# Sheet1.net
KiCad netlist of a schematic drawn in Altium Designer
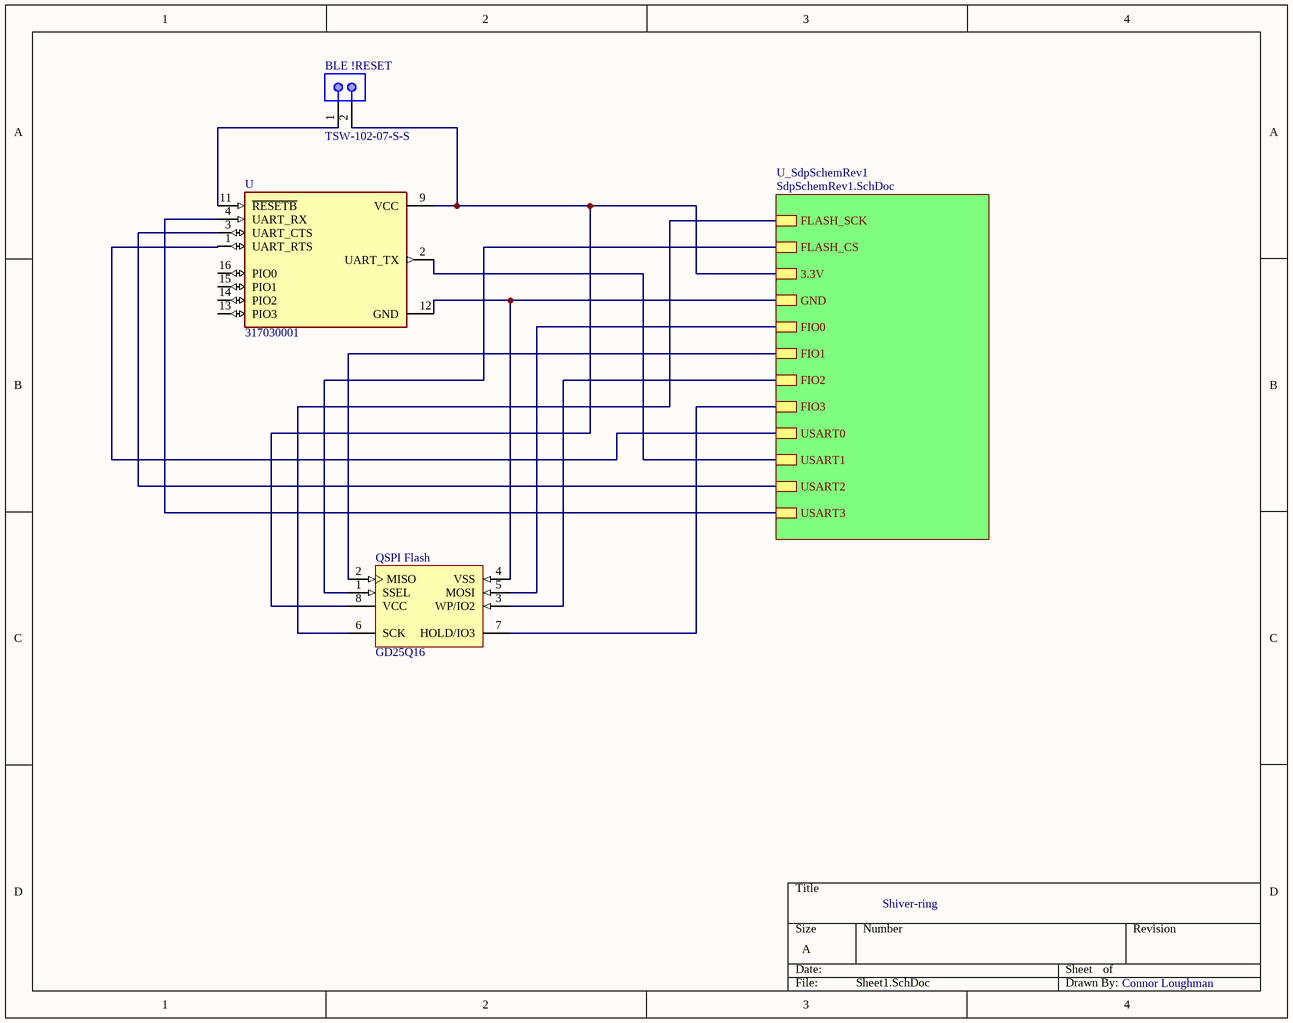
[diagram p0: Sheet1.SchDoc]

(export (version "E")
  (design (tool "Eeschema 10.0.6"))
  (components
    (comp (ref "BLE !RESET")
      (value "TSW-102-07-S-S")
      (footprint "SMTC-TSW-102-07-S-S")
      (fields (field (name "MANUFACTURER") "Samtec"))
      (libsource (lib "Altium Content Vault") (part "CN-1P-M-R2"))
    )
    (comp (ref "QSPI Flash")
      (value "GD25Q16")
      (footprint "MICT-MN-8_N")
      (fields
        (field (name "VOLTAGE") "2.7V-3.6V")
        (field (name "MANUFACTURER") "Micron")
        (field (name "PARTNUMBER") "M45PE10-VMN6P")
      )
      (libsource (lib "Altium Content Vault") (part "MICT-M45PE10-VMN-8"))
    )
    (comp (ref "U")
      (value "317030001")
      (footprint "XCVR_317030001")
      (description "Bluetooth Bluetooth v4.0 Transceiver Module 2.4GHz Integrated, Trace Surface Mount")
      (fields (field (name "MF") "Seeed Technology") (field (name "DIGI-KEY_PART_NUMBER") "1597-1359-ND"))
      (libsource (lib "317030001") (part "317030001"))
    )
  )
  (nets
    (net (code "1") (name "/3.3V") (class "Default")
      (node (ref "BLE !RESET") (pin "2") (pinfunction "2_2") (pintype "passive"))
      (node (ref "QSPI Flash") (pin "8") (pinfunction "VCC_8") (pintype "tri_state"))
      (node (ref "U") (pin "9") (pinfunction "VCC_9") (pintype "power_in"))
    )
    (net (code "2") (name "/FIO0") (class "Default")
      (node (ref "QSPI Flash") (pin "5") (pinfunction "MOSI_5") (pintype "input"))
    )
    (net (code "3") (name "/FIO1") (class "Default")
      (node (ref "QSPI Flash") (pin "2") (pinfunction "MISO_2") (pintype "input"))
    )
    (net (code "4") (name "/FIO2") (class "Default")
      (node (ref "QSPI Flash") (pin "3") (pinfunction "WP/IO2_3") (pintype "input"))
    )
    (net (code "5") (name "/FIO3") (class "Default")
      (node (ref "QSPI Flash") (pin "7") (pinfunction "HOLD/IO3_7") (pintype "power_in"))
    )
    (net (code "6") (name "/FLASH_CS") (class "Default")
      (node (ref "QSPI Flash") (pin "1") (pinfunction "SSEL_1") (pintype "input"))
    )
    (net (code "7") (name "/FLASH_SCK") (class "Default")
      (node (ref "QSPI Flash") (pin "6") (pinfunction "SCK_6") (pintype "power_in"))
    )
    (net (code "8") (name "/GND") (class "Default")
      (node (ref "QSPI Flash") (pin "4") (pinfunction "VSS_4") (pintype "input"))
      (node (ref "U") (pin "12") (pinfunction "GND_12") (pintype "power_in"))
    )
    (net (code "9") (name "/USART0") (class "Default")
      (node (ref "U") (pin "1") (pinfunction "UART_RTS_1") (pintype "bidirectional"))
    )
    (net (code "10") (name "/USART1") (class "Default")
      (node (ref "U") (pin "2") (pinfunction "UART_TX_2") (pintype "output"))
    )
    (net (code "11") (name "/USART2") (class "Default")
      (node (ref "U") (pin "3") (pinfunction "UART_CTS_3") (pintype "bidirectional"))
    )
    (net (code "12") (name "/USART3") (class "Default")
      (node (ref "U") (pin "4") (pinfunction "UART_RX_4") (pintype "input"))
    )
    (net (code "13") (name "Net-(U-~{RESETB})") (class "Default")
      (node (ref "BLE !RESET") (pin "1") (pinfunction "1_1") (pintype "passive"))
      (node (ref "U") (pin "11") (pinfunction "~{RESETB}_11") (pintype "input"))
    )
    (net (code "14") (name "unconnected-(U-PIO0-Pad16)") (class "Default")
      (node (ref "U") (pin "16") (pinfunction "PIO0_16") (pintype "bidirectional"))
    )
    (net (code "15") (name "unconnected-(U-PIO1-Pad15)") (class "Default")
      (node (ref "U") (pin "15") (pinfunction "PIO1_15") (pintype "bidirectional"))
    )
    (net (code "16") (name "unconnected-(U-PIO2-Pad14)") (class "Default")
      (node (ref "U") (pin "14") (pinfunction "PIO2_14") (pintype "bidirectional"))
    )
    (net (code "17") (name "unconnected-(U-PIO3-Pad13)") (class "Default")
      (node (ref "U") (pin "13") (pinfunction "PIO3_13") (pintype "bidirectional"))
    )
  )
)
